# SCH_gaelpager-with-external-wifi-thing_2.net
KiCad netlist of a schematic drawn in EasyEDA
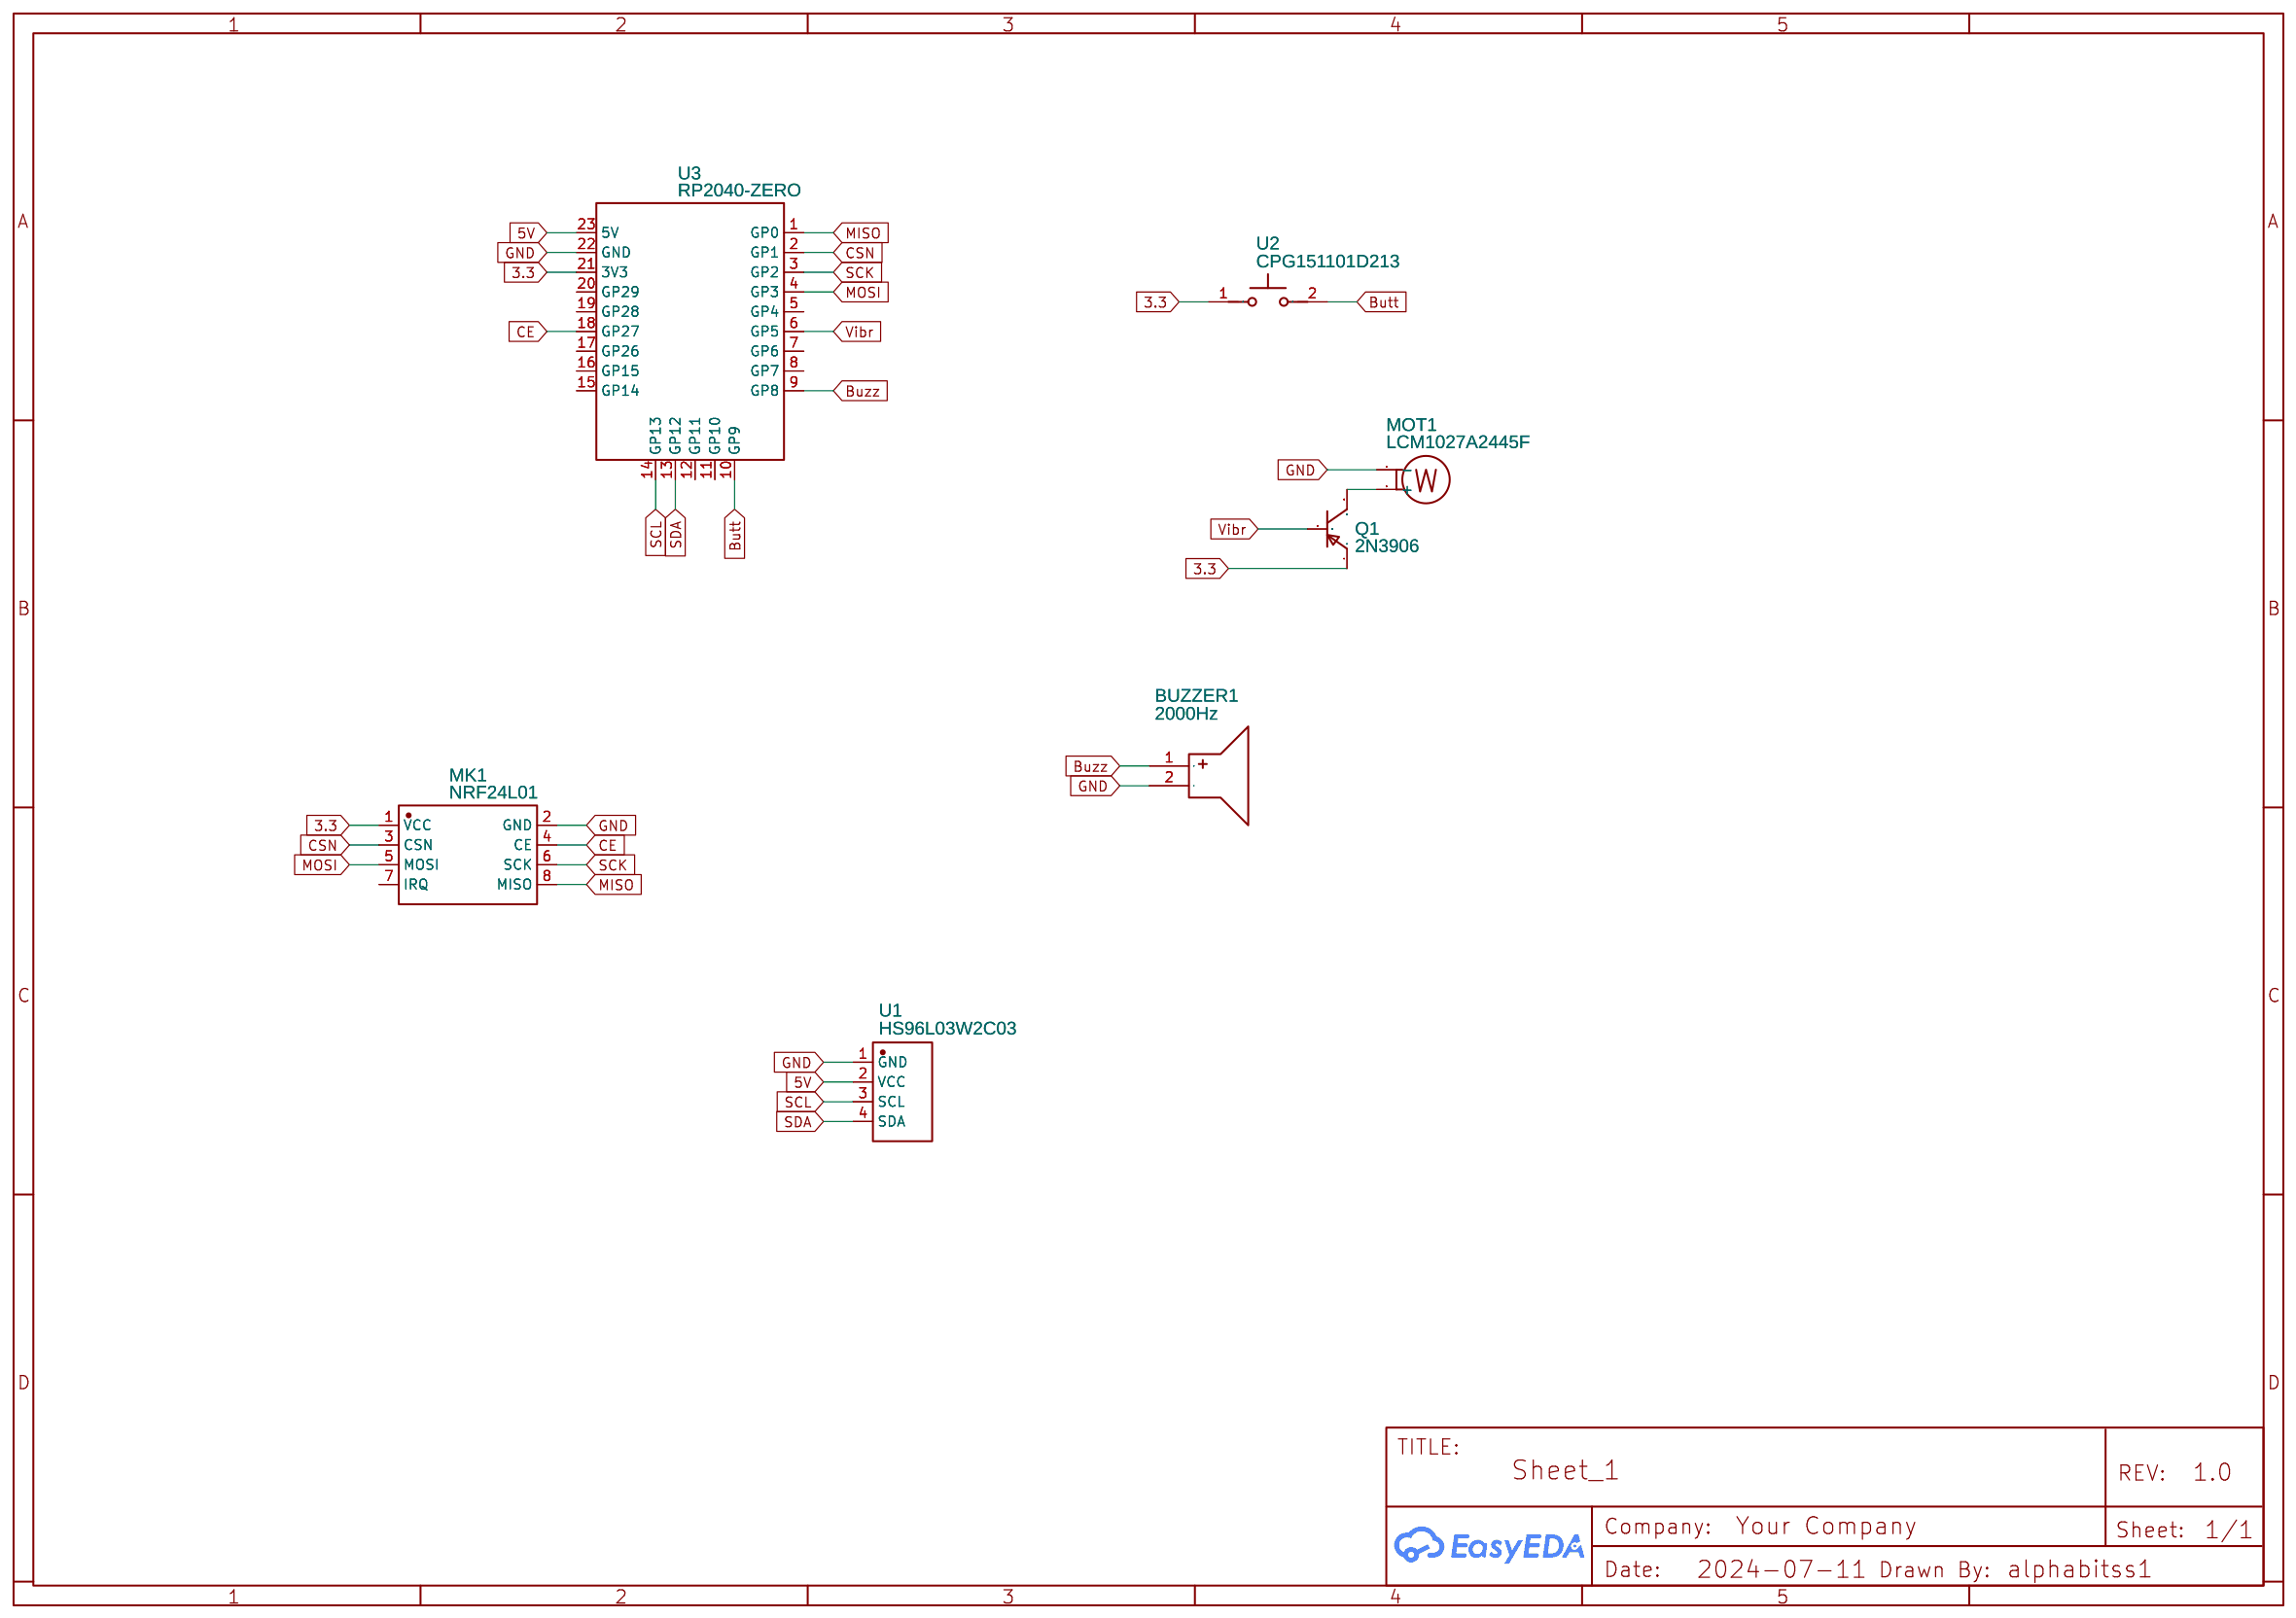
[diagram p0: schematic sheet]

(export (version "E")
  (design (tool "Eeschema 10.0.6"))
  (components
    (comp (ref "BUZZER1")
      (value "2000Hz")
      (fields (field (name "Manufacturer Part") "FS1265-05") (field (name "Manufacturer") "FUET(福声科技)"))
      (libsource (lib "") (part "FS1265-05"))
    )
    (comp (ref "MK1")
      (value "NRF24L01")
      (fields (field (name "Manufacturer Part") "NF-04") (field (name "Manufacturer") "Ai-Thinker(安信可)"))
      (libsource (lib "") (part "NRF24L01"))
    )
    (comp (ref "MOT1")
      (value "LCM1027A2445F")
      (fields (field (name "Manufacturer") "LEADER(立得)"))
      (libsource (lib "") (part "LCM1027A2445F"))
    )
    (comp (ref "Q1")
      (value "2N3906")
      (fields (field (name "Manufacturer") "CJ(江苏长电/长晶)"))
      (libsource (lib "") (part "2N3906"))
    )
    (comp (ref "U1")
      (value "HS96L03W2C03")
      (fields (field (name "Manufacturer") "HS(汉昇)"))
      (libsource (lib "") (part "HS96L03W2C03"))
    )
    (comp (ref "U2")
      (value "CPG151101D213")
      (fields (field (name "Manufacturer") "Kailh(凯华)"))
      (libsource (lib "") (part "CPG151101D213"))
    )
    (comp (ref "U3")
      (value "RP2040-ZERO")
      (fields
        (field (name "Manufacturer Part") "RP2040-Zero")
        (field (name "Manufacturer") "Waveshare(微雪电子)")
      )
      (libsource (lib "") (part "RP2040-ZERO"))
    )
  )
  (nets
    (net (code "1") (name "3.3") (class "Default")
      (node (ref "MK1") (pin "1") (pinfunction "VCC_1") (pintype "unspecified"))
      (node (ref "Q1") (pin "1") (pinfunction "E_1") (pintype "unspecified"))
      (node (ref "U2") (pin "1") (pinfunction "1_1") (pintype "unspecified"))
      (node (ref "U3") (pin "21") (pinfunction "3V3_21") (pintype "unspecified"))
    )
    (net (code "2") (name "5V") (class "Default")
      (node (ref "U1") (pin "2") (pinfunction "VCC_2") (pintype "unspecified"))
      (node (ref "U3") (pin "23") (pinfunction "5V_23") (pintype "unspecified"))
    )
    (net (code "3") (name "Butt") (class "Default")
      (node (ref "U2") (pin "2") (pinfunction "2_2") (pintype "unspecified"))
      (node (ref "U3") (pin "10") (pinfunction "GP9_10") (pintype "unspecified"))
    )
    (net (code "4") (name "Buzz") (class "Default")
      (node (ref "BUZZER1") (pin "1") (pinfunction "+_1") (pintype "unspecified"))
      (node (ref "U3") (pin "9") (pinfunction "GP8_9") (pintype "unspecified"))
    )
    (net (code "5") (name "CE") (class "Default")
      (node (ref "MK1") (pin "4") (pinfunction "CE_4") (pintype "unspecified"))
      (node (ref "U3") (pin "18") (pinfunction "GP27_18") (pintype "unspecified"))
    )
    (net (code "6") (name "CSN") (class "Default")
      (node (ref "MK1") (pin "3") (pinfunction "CSN_3") (pintype "unspecified"))
      (node (ref "U3") (pin "2") (pinfunction "GP1_2") (pintype "unspecified"))
    )
    (net (code "7") (name "GND") (class "Default")
      (node (ref "BUZZER1") (pin "2") (pinfunction "-_2") (pintype "unspecified"))
      (node (ref "MK1") (pin "2") (pinfunction "GND_2") (pintype "unspecified"))
      (node (ref "MOT1") (pin "1") (pinfunction "-_1") (pintype "unspecified"))
      (node (ref "U1") (pin "1") (pinfunction "GND_1") (pintype "unspecified"))
      (node (ref "U3") (pin "22") (pinfunction "GND_22") (pintype "unspecified"))
    )
    (net (code "8") (name "MISO") (class "Default")
      (node (ref "MK1") (pin "8") (pinfunction "MISO_8") (pintype "unspecified"))
      (node (ref "U3") (pin "1") (pinfunction "GP0_1") (pintype "unspecified"))
    )
    (net (code "9") (name "MOSI") (class "Default")
      (node (ref "MK1") (pin "5") (pinfunction "MOSI_5") (pintype "unspecified"))
      (node (ref "U3") (pin "4") (pinfunction "GP3_4") (pintype "unspecified"))
    )
    (net (code "10") (name "Net-(MOT1-+)") (class "Default")
      (node (ref "MOT1") (pin "2") (pinfunction "+_2") (pintype "unspecified"))
      (node (ref "Q1") (pin "3") (pinfunction "C_3") (pintype "unspecified"))
    )
    (net (code "11") (name "SCK") (class "Default")
      (node (ref "MK1") (pin "6") (pinfunction "SCK_6") (pintype "unspecified"))
      (node (ref "U3") (pin "3") (pinfunction "GP2_3") (pintype "unspecified"))
    )
    (net (code "12") (name "SCL") (class "Default")
      (node (ref "U1") (pin "3") (pinfunction "SCL_3") (pintype "unspecified"))
      (node (ref "U3") (pin "14") (pinfunction "GP13_14") (pintype "unspecified"))
    )
    (net (code "13") (name "SDA") (class "Default")
      (node (ref "U1") (pin "4") (pinfunction "SDA_4") (pintype "unspecified"))
      (node (ref "U3") (pin "13") (pinfunction "GP12_13") (pintype "unspecified"))
    )
    (net (code "14") (name "Vibr") (class "Default")
      (node (ref "Q1") (pin "2") (pinfunction "B_2") (pintype "unspecified"))
      (node (ref "U3") (pin "6") (pinfunction "GP5_6") (pintype "unspecified"))
    )
    (net (code "15") (name "unconnected-(MK1-IRQ-Pad7)") (class "Default")
      (node (ref "MK1") (pin "7") (pinfunction "IRQ_7") (pintype "unspecified"))
    )
    (net (code "16") (name "unconnected-(U3-GP4-Pad5)") (class "Default")
      (node (ref "U3") (pin "5") (pinfunction "GP4_5") (pintype "unspecified"))
    )
    (net (code "17") (name "unconnected-(U3-GP6-Pad7)") (class "Default")
      (node (ref "U3") (pin "7") (pinfunction "GP6_7") (pintype "unspecified"))
    )
    (net (code "18") (name "unconnected-(U3-GP7-Pad8)") (class "Default")
      (node (ref "U3") (pin "8") (pinfunction "GP7_8") (pintype "unspecified"))
    )
    (net (code "19") (name "unconnected-(U3-GP10-Pad11)") (class "Default")
      (node (ref "U3") (pin "11") (pinfunction "GP10_11") (pintype "unspecified"))
    )
    (net (code "20") (name "unconnected-(U3-GP11-Pad12)") (class "Default")
      (node (ref "U3") (pin "12") (pinfunction "GP11_12") (pintype "unspecified"))
    )
    (net (code "21") (name "unconnected-(U3-GP14-Pad15)") (class "Default")
      (node (ref "U3") (pin "15") (pinfunction "GP14_15") (pintype "unspecified"))
    )
    (net (code "22") (name "unconnected-(U3-GP15-Pad16)") (class "Default")
      (node (ref "U3") (pin "16") (pinfunction "GP15_16") (pintype "unspecified"))
    )
    (net (code "23") (name "unconnected-(U3-GP26-Pad17)") (class "Default")
      (node (ref "U3") (pin "17") (pinfunction "GP26_17") (pintype "unspecified"))
    )
    (net (code "24") (name "unconnected-(U3-GP28-Pad19)") (class "Default")
      (node (ref "U3") (pin "19") (pinfunction "GP28_19") (pintype "unspecified"))
    )
    (net (code "25") (name "unconnected-(U3-GP29-Pad20)") (class "Default")
      (node (ref "U3") (pin "20") (pinfunction "GP29_20") (pintype "unspecified"))
    )
  )
)
